# sensor_board3.net
KiCad netlist of a schematic drawn in EAGLE
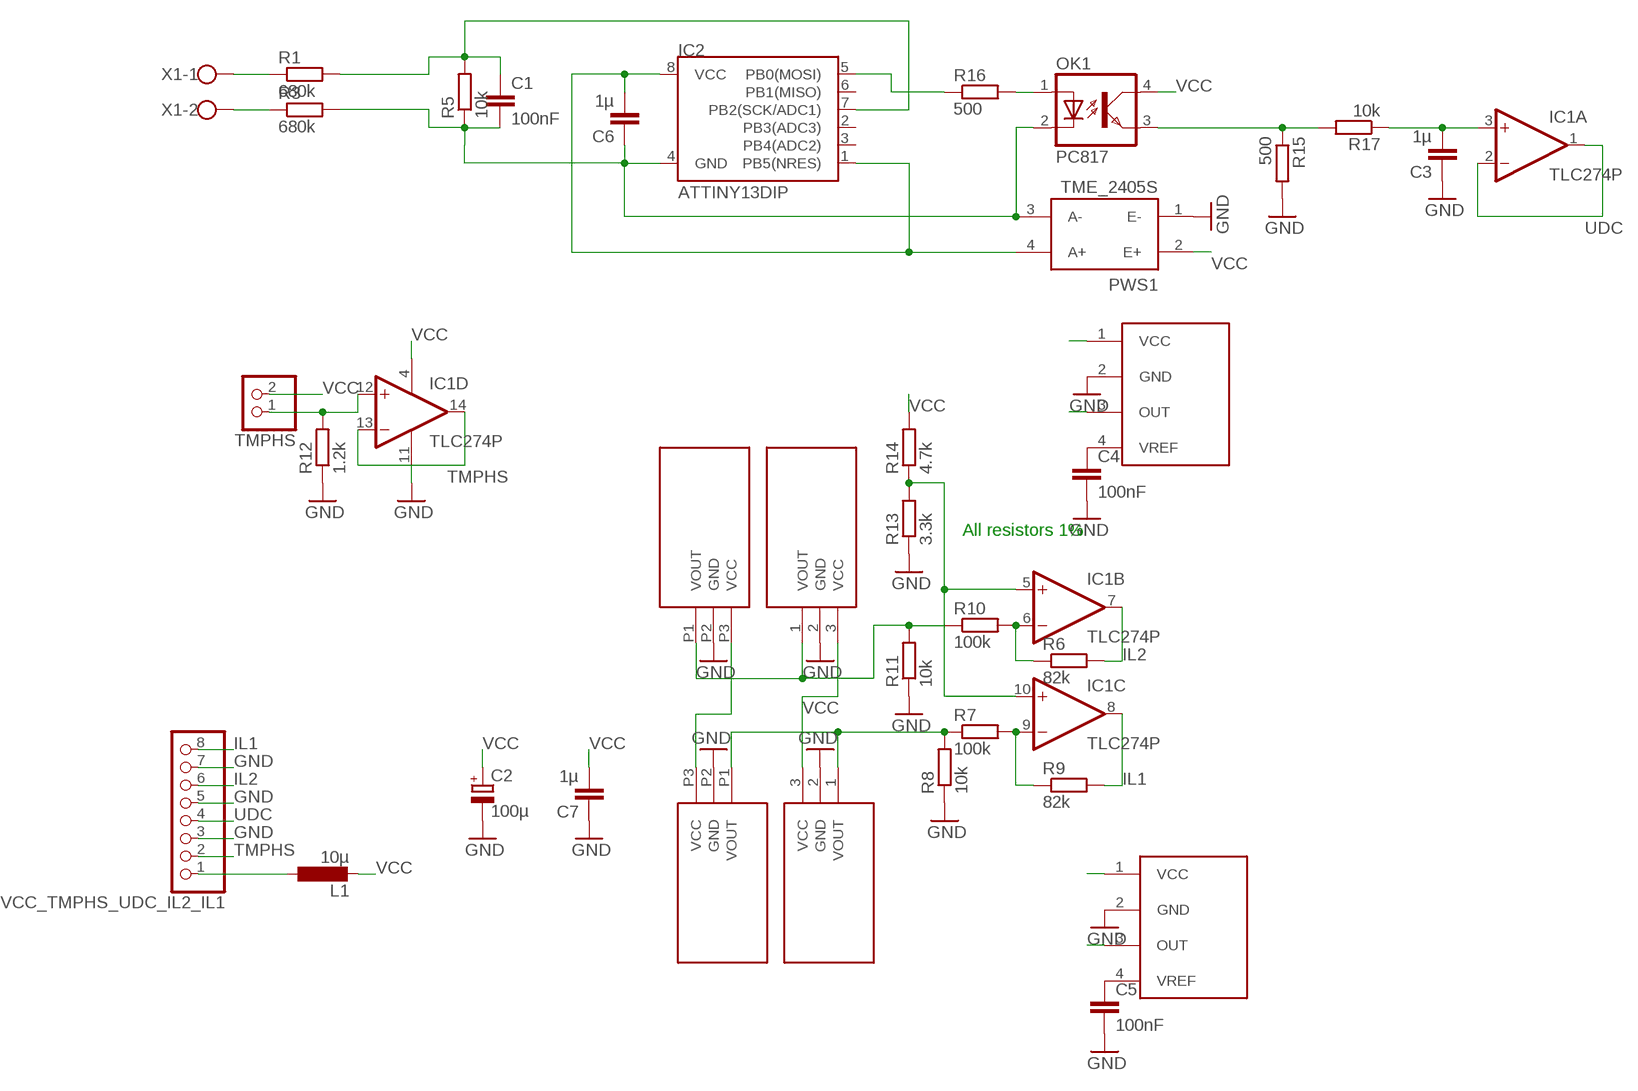
[diagram p0: schematic, sheet 1]

(export (version "E")
  (design (tool "Eeschema 10.0.6"))
  (components
    (comp (ref "C1")
      (value "100nF")
      (footprint "eagle-import:C025-024X044")
      (libsource (lib "eagle-import") (part "C-EU025-024X044"))
    )
    (comp (ref "C2")
      (value "100µ")
      (footprint "eagle-import:E2,5-6E")
      (libsource (lib "eagle-import") (part "CPOL-EUE2,5-6E"))
    )
    (comp (ref "C3")
      (value "1µ")
      (footprint "eagle-import:C025-024X044")
      (libsource (lib "eagle-import") (part "C-EU025-024X044"))
    )
    (comp (ref "C4")
      (value "100nF")
      (footprint "eagle-import:C025-024X044")
      (libsource (lib "eagle-import") (part "C-EU025-024X044"))
    )
    (comp (ref "C5")
      (value "100nF")
      (footprint "eagle-import:C025-024X044")
      (libsource (lib "eagle-import") (part "C-EU025-024X044"))
    )
    (comp (ref "C6")
      (value "1µ")
      (footprint "eagle-import:C025-024X044")
      (libsource (lib "eagle-import") (part "C-EU025-024X044"))
    )
    (comp (ref "C7")
      (value "1µ")
      (footprint "eagle-import:C025-024X044")
      (libsource (lib "eagle-import") (part "C-EU025-024X044"))
    )
    (comp (ref "IC1")
      (value "TLC274P")
      (footprint "eagle-import:DIL14")
      (libsource (lib "eagle-import") (part "TLC274P"))
    )
    (comp (ref "IC2")
      (value "ATTINY13DIP")
      (footprint "eagle-import:DIP08")
      (libsource (lib "eagle-import") (part "ATTINY13DIP"))
    )
    (comp (ref "L1")
      (value "10µ")
      (footprint "eagle-import:0207_12")
      (libsource (lib "eagle-import") (part "L-EU0207/12"))
    )
    (comp (ref "OK1")
      (value "PC817")
      (footprint "eagle-import:DIL04")
      (fields (field (name "MPN") "PC817X4J000F"))
      (libsource (lib "eagle-import") (part "PC817"))
    )
    (comp (ref "PWS1")
      (value "TME_2405S")
      (footprint "eagle-import:TMEXXXXS")
      (fields (field (name "MPN") "TME 2405S"))
      (libsource (lib "eagle-import") (part "TME_S2405"))
    )
    (comp (ref "R1")
      (value "680k")
      (footprint "eagle-import:0207_10")
      (libsource (lib "eagle-import") (part "R-EU_0207/10"))
    )
    (comp (ref "R3")
      (value "680k")
      (footprint "eagle-import:0207_10")
      (libsource (lib "eagle-import") (part "R-EU_0207/10"))
    )
    (comp (ref "R5")
      (value "10k")
      (footprint "eagle-import:0207_10")
      (libsource (lib "eagle-import") (part "R-EU_0207/10"))
    )
    (comp (ref "R6")
      (value "82k")
      (footprint "eagle-import:0207_10")
      (libsource (lib "eagle-import") (part "R-EU_0207/10"))
    )
    (comp (ref "R7")
      (value "100k")
      (footprint "eagle-import:0207_10")
      (libsource (lib "eagle-import") (part "R-EU_0207/10"))
    )
    (comp (ref "R8")
      (value "10k")
      (footprint "eagle-import:0207_10")
      (libsource (lib "eagle-import") (part "R-EU_0207/10"))
    )
    (comp (ref "R9")
      (value "82k")
      (footprint "eagle-import:0207_10")
      (libsource (lib "eagle-import") (part "R-EU_0207/10"))
    )
    (comp (ref "R10")
      (value "100k")
      (footprint "eagle-import:0207_10")
      (libsource (lib "eagle-import") (part "R-EU_0207/10"))
    )
    (comp (ref "R11")
      (value "10k")
      (footprint "eagle-import:0207_10")
      (libsource (lib "eagle-import") (part "R-EU_0207/10"))
    )
    (comp (ref "R12")
      (value "1.2k")
      (footprint "eagle-import:0207_10")
      (libsource (lib "eagle-import") (part "R-EU_0207/10"))
    )
    (comp (ref "R13")
      (value "3.3k")
      (footprint "eagle-import:0207_10")
      (libsource (lib "eagle-import") (part "R-EU_0207/10"))
    )
    (comp (ref "R14")
      (value "4.7k")
      (footprint "eagle-import:0207_10")
      (libsource (lib "eagle-import") (part "R-EU_0207/10"))
    )
    (comp (ref "R15")
      (value "500")
      (footprint "eagle-import:0207_10")
      (libsource (lib "eagle-import") (part "R-EU_0207/10"))
    )
    (comp (ref "R16")
      (value "500")
      (footprint "eagle-import:0207_10")
      (libsource (lib "eagle-import") (part "R-EU_0207/10"))
    )
    (comp (ref "R17")
      (value "10k")
      (footprint "eagle-import:0207_10")
      (libsource (lib "eagle-import") (part "R-EU_0207/10"))
    )
    (comp (ref "TMPHS")
      (value "PINHD-1X2")
      (footprint "eagle-import:1X02")
      (libsource (lib "eagle-import") (part "PINHD-1X2"))
    )
    (comp (ref "U$1")
      (value "TAMURA_L01Z_S05")
      (footprint "eagle-import:TAMURA_L01Z_S05")
      (libsource (lib "eagle-import") (part "TAMURA_L01Z_S05"))
    )
    (comp (ref "U$2")
      (value "TAMURA_L01Z_S05")
      (footprint "eagle-import:TAMURA_L01Z_S05")
      (libsource (lib "eagle-import") (part "TAMURA_L01Z_S05"))
    )
    (comp (ref "U$3")
      (value "HTFS")
      (footprint "eagle-import:HTFS")
      (libsource (lib "eagle-import") (part "HTFS"))
    )
    (comp (ref "U$4")
      (value "HTFS")
      (footprint "eagle-import:HTFS")
      (libsource (lib "eagle-import") (part "HTFS"))
    )
    (comp (ref "U$5")
      (value "TAMURA_L06P_S05L06P")
      (footprint "eagle-import:TAMURA_L06P_S05")
      (libsource (lib "eagle-import") (part "TAMURA_L06P_S05L06P"))
    )
    (comp (ref "U$6")
      (value "TAMURA_L06P_S05L06P")
      (footprint "eagle-import:TAMURA_L06P_S05")
      (libsource (lib "eagle-import") (part "TAMURA_L06P_S05L06P"))
    )
    (comp (ref "VCC_TMPHS_UDC_IL2_IL1")
      (value "PINHD-1X8")
      (footprint "eagle-import:1X08")
      (libsource (lib "eagle-import") (part "PINHD-1X8"))
    )
    (comp (ref "X1")
      (value "W237-102")
      (footprint "eagle-import:W237-102")
      (fields (field (name "MPN") "237-102"))
      (libsource (lib "eagle-import") (part "W237-102"))
    )
  )
  (nets
    (net (code "1") (name "/IL1") (class "Default")
      (node (ref "IC1") (pin "8") (pinfunction "OUT_8") (pintype "output"))
      (node (ref "R9") (pin "2") (pinfunction "2_2") (pintype "passive"))
      (node (ref "VCC_TMPHS_UDC_IL2_IL1") (pin "8") (pinfunction "8_8") (pintype "passive"))
    )
    (net (code "2") (name "/IL2") (class "Default")
      (node (ref "IC1") (pin "7") (pinfunction "OUT_7") (pintype "output"))
      (node (ref "R6") (pin "2") (pinfunction "2_2") (pintype "passive"))
      (node (ref "VCC_TMPHS_UDC_IL2_IL1") (pin "6") (pinfunction "6_6") (pintype "passive"))
    )
    (net (code "3") (name "/TMPHS") (class "Default")
      (node (ref "IC1") (pin "13") (pinfunction "-IN_13") (pintype "input"))
      (node (ref "IC1") (pin "14") (pinfunction "OUT_14") (pintype "output"))
      (node (ref "VCC_TMPHS_UDC_IL2_IL1") (pin "2") (pinfunction "2_2") (pintype "passive"))
    )
    (net (code "4") (name "/UDC") (class "Default")
      (node (ref "IC1") (pin "1") (pinfunction "OUT_1") (pintype "output"))
      (node (ref "IC1") (pin "2") (pinfunction "-IN_2") (pintype "input"))
      (node (ref "VCC_TMPHS_UDC_IL2_IL1") (pin "4") (pinfunction "4_4") (pintype "passive"))
    )
    (net (code "5") (name "/VCC") (class "Default")
      (node (ref "C2") (pin "+") (pinfunction "+_+") (pintype "passive"))
      (node (ref "C7") (pin "2") (pinfunction "2_2") (pintype "passive"))
      (node (ref "IC1") (pin "4") (pinfunction "V+_4") (pintype "power_in"))
      (node (ref "L1") (pin "2") (pinfunction "2_2") (pintype "passive"))
      (node (ref "OK1") (pin "4") (pinfunction "COL_4") (pintype "passive"))
      (node (ref "PWS1") (pin "2") (pinfunction "E+_2") (pintype "input"))
      (node (ref "R14") (pin "2") (pinfunction "2_2") (pintype "passive"))
      (node (ref "TMPHS") (pin "2") (pinfunction "2_2") (pintype "passive"))
      (node (ref "U$1") (pin "3") (pinfunction "VCC_3") (pintype "bidirectional"))
      (node (ref "U$2") (pin "3") (pinfunction "VCC_3") (pintype "bidirectional"))
      (node (ref "U$3") (pin "1") (pinfunction "VCC_1") (pintype "bidirectional"))
      (node (ref "U$4") (pin "1") (pinfunction "VCC_1") (pintype "bidirectional"))
      (node (ref "U$5") (pin "P3") (pinfunction "VCC_P3") (pintype "bidirectional"))
      (node (ref "U$6") (pin "P3") (pinfunction "VCC_P3") (pintype "bidirectional"))
    )
    (net (code "6") (name "/VOUT1") (class "Default")
      (node (ref "R7") (pin "1") (pinfunction "1_1") (pintype "passive"))
      (node (ref "R8") (pin "2") (pinfunction "2_2") (pintype "passive"))
      (node (ref "U$2") (pin "1") (pinfunction "VOUT_1") (pintype "bidirectional"))
      (node (ref "U$4") (pin "3") (pinfunction "OUT_3") (pintype "bidirectional"))
      (node (ref "U$6") (pin "P1") (pinfunction "VOUT_P1") (pintype "bidirectional"))
    )
    (net (code "7") (name "/VOUT2") (class "Default")
      (node (ref "R10") (pin "1") (pinfunction "1_1") (pintype "passive"))
      (node (ref "R11") (pin "2") (pinfunction "2_2") (pintype "passive"))
      (node (ref "U$1") (pin "1") (pinfunction "VOUT_1") (pintype "bidirectional"))
      (node (ref "U$3") (pin "3") (pinfunction "OUT_3") (pintype "bidirectional"))
      (node (ref "U$5") (pin "P1") (pinfunction "VOUT_P1") (pintype "bidirectional"))
    )
    (net (code "8") (name "GND") (class "Default")
      (node (ref "C2") (pin "-") (pinfunction "-_-") (pintype "passive"))
      (node (ref "C3") (pin "1") (pinfunction "1_1") (pintype "passive"))
      (node (ref "C4") (pin "2") (pinfunction "2_2") (pintype "passive"))
      (node (ref "C5") (pin "2") (pinfunction "2_2") (pintype "passive"))
      (node (ref "C7") (pin "1") (pinfunction "1_1") (pintype "passive"))
      (node (ref "IC1") (pin "11") (pinfunction "V-_11") (pintype "power_in"))
      (node (ref "PWS1") (pin "1") (pinfunction "E-_1") (pintype "input"))
      (node (ref "R11") (pin "1") (pinfunction "1_1") (pintype "passive"))
      (node (ref "R12") (pin "1") (pinfunction "1_1") (pintype "passive"))
      (node (ref "R13") (pin "1") (pinfunction "1_1") (pintype "passive"))
      (node (ref "R15") (pin "2") (pinfunction "2_2") (pintype "passive"))
      (node (ref "R8") (pin "1") (pinfunction "1_1") (pintype "passive"))
      (node (ref "U$1") (pin "2") (pinfunction "GND_2") (pintype "bidirectional"))
      (node (ref "U$2") (pin "2") (pinfunction "GND_2") (pintype "bidirectional"))
      (node (ref "U$3") (pin "2") (pinfunction "GND_2") (pintype "bidirectional"))
      (node (ref "U$4") (pin "2") (pinfunction "GND_2") (pintype "bidirectional"))
      (node (ref "U$5") (pin "P2") (pinfunction "GND_P2") (pintype "bidirectional"))
      (node (ref "U$6") (pin "P2") (pinfunction "GND_P2") (pintype "bidirectional"))
      (node (ref "VCC_TMPHS_UDC_IL2_IL1") (pin "3") (pinfunction "3_3") (pintype "passive"))
      (node (ref "VCC_TMPHS_UDC_IL2_IL1") (pin "5") (pinfunction "5_5") (pintype "passive"))
      (node (ref "VCC_TMPHS_UDC_IL2_IL1") (pin "7") (pinfunction "7_7") (pintype "passive"))
    )
    (net (code "9") (name "Net-(IC1A-+IN)") (class "Default")
      (node (ref "C3") (pin "2") (pinfunction "2_2") (pintype "passive"))
      (node (ref "IC1") (pin "3") (pinfunction "+IN_3") (pintype "input"))
      (node (ref "R17") (pin "1") (pinfunction "1_1") (pintype "passive"))
    )
    (net (code "10") (name "Net-(IC1B-+IN)") (class "Default")
      (node (ref "IC1") (pin "10") (pinfunction "+IN_10") (pintype "input"))
      (node (ref "IC1") (pin "5") (pinfunction "+IN_5") (pintype "input"))
      (node (ref "R13") (pin "2") (pinfunction "2_2") (pintype "passive"))
      (node (ref "R14") (pin "1") (pinfunction "1_1") (pintype "passive"))
    )
    (net (code "11") (name "Net-(IC1B--IN)") (class "Default")
      (node (ref "IC1") (pin "6") (pinfunction "-IN_6") (pintype "input"))
      (node (ref "R10") (pin "2") (pinfunction "2_2") (pintype "passive"))
      (node (ref "R6") (pin "1") (pinfunction "1_1") (pintype "passive"))
    )
    (net (code "12") (name "Net-(IC1C--IN)") (class "Default")
      (node (ref "IC1") (pin "9") (pinfunction "-IN_9") (pintype "input"))
      (node (ref "R7") (pin "2") (pinfunction "2_2") (pintype "passive"))
      (node (ref "R9") (pin "1") (pinfunction "1_1") (pintype "passive"))
    )
    (net (code "13") (name "Net-(IC1D-+IN)") (class "Default")
      (node (ref "IC1") (pin "12") (pinfunction "+IN_12") (pintype "input"))
      (node (ref "R12") (pin "2") (pinfunction "2_2") (pintype "passive"))
      (node (ref "TMPHS") (pin "1") (pinfunction "1_1") (pintype "passive"))
    )
    (net (code "14") (name "Net-(IC2-GND)") (class "Default")
      (node (ref "C1") (pin "2") (pinfunction "2_2") (pintype "passive"))
      (node (ref "C6") (pin "1") (pinfunction "1_1") (pintype "passive"))
      (node (ref "IC2") (pin "4") (pinfunction "GND_4") (pintype "bidirectional"))
      (node (ref "OK1") (pin "2") (pinfunction "C_2") (pintype "passive"))
      (node (ref "PWS1") (pin "3") (pinfunction "A-_3") (pintype "output"))
      (node (ref "R3") (pin "2") (pinfunction "2_2") (pintype "passive"))
      (node (ref "R5") (pin "1") (pinfunction "1_1") (pintype "passive"))
    )
    (net (code "15") (name "Net-(IC2-PB0(MOSI))") (class "Default")
      (node (ref "IC2") (pin "5") (pinfunction "PB0(MOSI)_5") (pintype "bidirectional"))
      (node (ref "R16") (pin "1") (pinfunction "1_1") (pintype "passive"))
    )
    (net (code "16") (name "Net-(IC2-PB2(SCK{slash}ADC1))") (class "Default")
      (node (ref "C1") (pin "1") (pinfunction "1_1") (pintype "passive"))
      (node (ref "IC2") (pin "7") (pinfunction "PB2(SCK/ADC1)_7") (pintype "bidirectional"))
      (node (ref "R1") (pin "2") (pinfunction "2_2") (pintype "passive"))
      (node (ref "R5") (pin "2") (pinfunction "2_2") (pintype "passive"))
    )
    (net (code "17") (name "Net-(IC2-PB5(NRES))") (class "Default")
      (node (ref "C6") (pin "2") (pinfunction "2_2") (pintype "passive"))
      (node (ref "IC2") (pin "1") (pinfunction "PB5(NRES)_1") (pintype "bidirectional"))
      (node (ref "IC2") (pin "8") (pinfunction "VCC_8") (pintype "bidirectional"))
      (node (ref "PWS1") (pin "4") (pinfunction "A+_4") (pintype "output"))
    )
    (net (code "18") (name "Net-(L1-Pad1)") (class "Default")
      (node (ref "L1") (pin "1") (pinfunction "1_1") (pintype "passive"))
      (node (ref "VCC_TMPHS_UDC_IL2_IL1") (pin "1") (pinfunction "1_1") (pintype "passive"))
    )
    (net (code "19") (name "Net-(OK1-A)") (class "Default")
      (node (ref "OK1") (pin "1") (pinfunction "A_1") (pintype "passive"))
      (node (ref "R16") (pin "2") (pinfunction "2_2") (pintype "passive"))
    )
    (net (code "20") (name "Net-(OK1-EMIT)") (class "Default")
      (node (ref "OK1") (pin "3") (pinfunction "EMIT_3") (pintype "passive"))
      (node (ref "R15") (pin "1") (pinfunction "1_1") (pintype "passive"))
      (node (ref "R17") (pin "2") (pinfunction "2_2") (pintype "passive"))
    )
    (net (code "21") (name "Net-(U$3-VREF)") (class "Default")
      (node (ref "C4") (pin "1") (pinfunction "1_1") (pintype "passive"))
      (node (ref "U$3") (pin "4") (pinfunction "VREF_4") (pintype "bidirectional"))
    )
    (net (code "22") (name "Net-(U$4-VREF)") (class "Default")
      (node (ref "C5") (pin "1") (pinfunction "1_1") (pintype "passive"))
      (node (ref "U$4") (pin "4") (pinfunction "VREF_4") (pintype "bidirectional"))
    )
    (net (code "23") (name "Net-(X1A-KL)") (class "Default")
      (node (ref "R1") (pin "1") (pinfunction "1_1") (pintype "passive"))
      (node (ref "X1") (pin "1") (pinfunction "KL_1") (pintype "passive"))
    )
    (net (code "24") (name "Net-(X1B-KL)") (class "Default")
      (node (ref "R3") (pin "1") (pinfunction "1_1") (pintype "passive"))
      (node (ref "X1") (pin "2") (pinfunction "KL_2") (pintype "passive"))
    )
    (net (code "25") (name "unconnected-(IC2-PB1(MISO)-Pad6)") (class "Default")
      (node (ref "IC2") (pin "6") (pinfunction "PB1(MISO)_6") (pintype "bidirectional"))
    )
    (net (code "26") (name "unconnected-(IC2-PB3(ADC3)-Pad2)") (class "Default")
      (node (ref "IC2") (pin "2") (pinfunction "PB3(ADC3)_2") (pintype "bidirectional"))
    )
    (net (code "27") (name "unconnected-(IC2-PB4(ADC2)-Pad3)") (class "Default")
      (node (ref "IC2") (pin "3") (pinfunction "PB4(ADC2)_3") (pintype "bidirectional"))
    )
  )
)
